# lab07.net
KiCad netlist of a schematic drawn in EAGLE
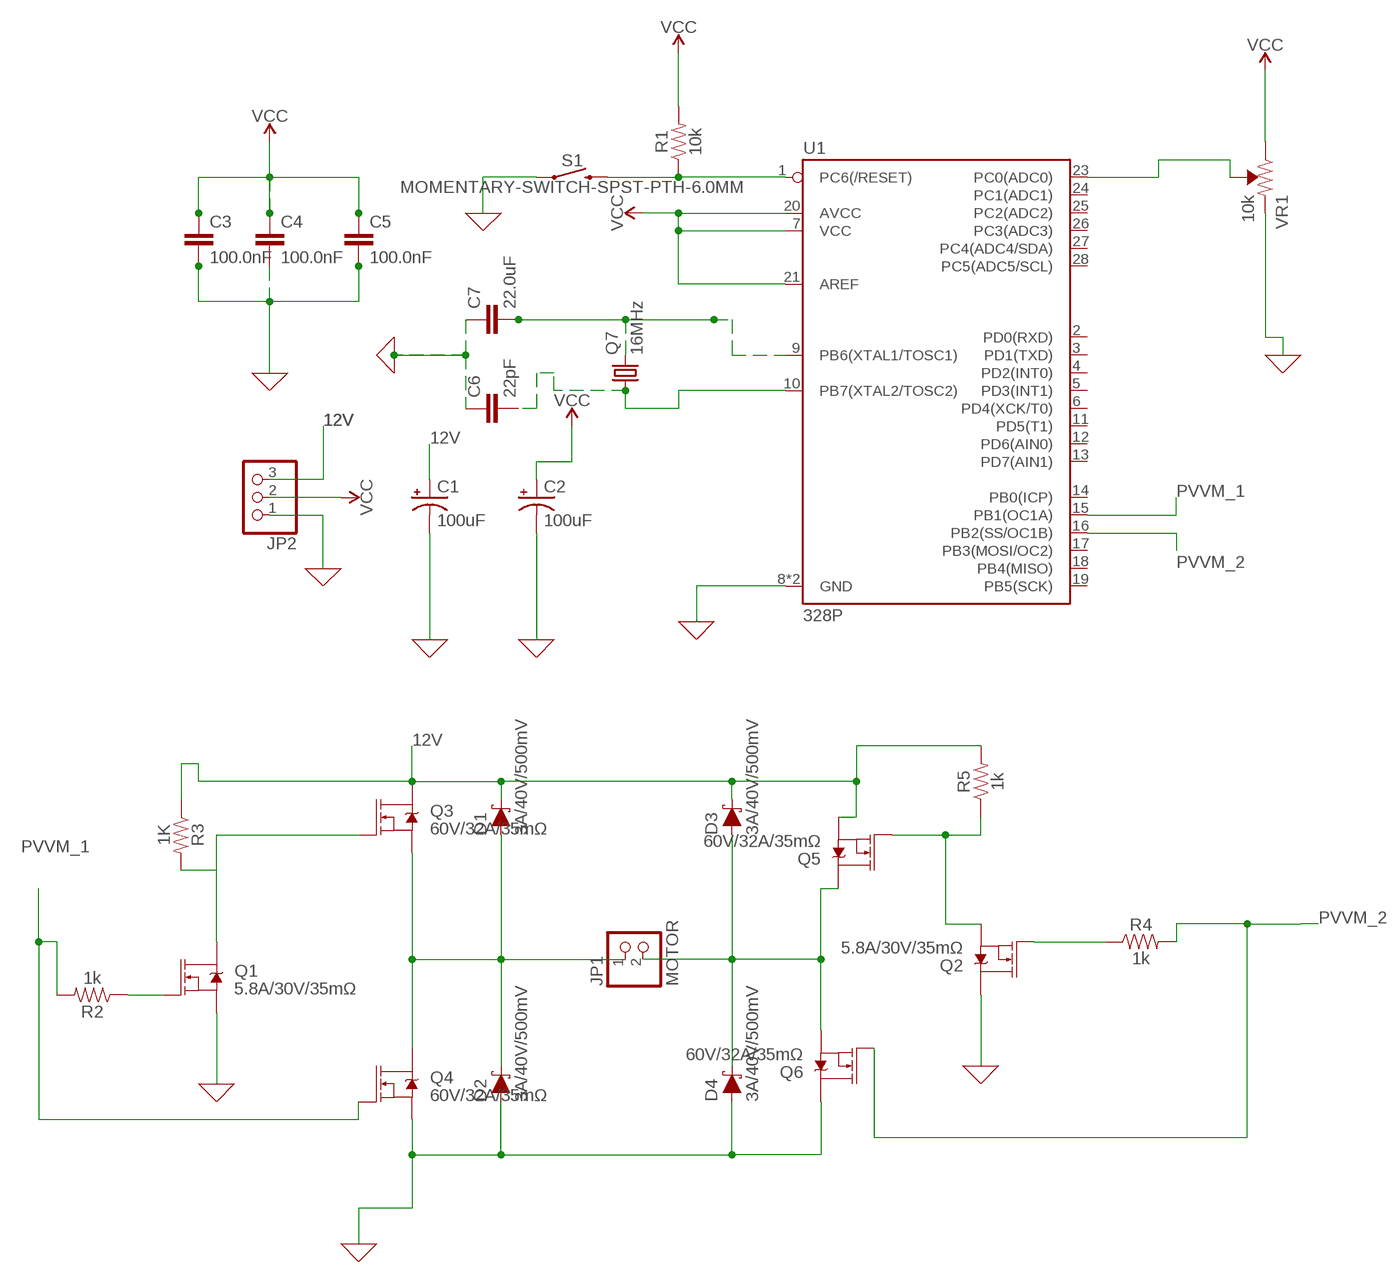
[diagram p0: schematic, sheet 1]

(export (version "E")
  (design (tool "Eeschema 10.0.6"))
  (components
    (comp (ref "C1")
      (value "100uF")
      (footprint "eagle-import:CPOL-RADIAL-2.5MM-5MM")
      (libsource (lib "eagle-import") (part "10UF-POLAR-RADIAL-2.5MM-25V-20%"))
    )
    (comp (ref "C2")
      (value "100uF")
      (footprint "eagle-import:CPOL-RADIAL-2.5MM-5MM")
      (libsource (lib "eagle-import") (part "10UF-POLAR-RADIAL-2.5MM-25V-20%"))
    )
    (comp (ref "C3")
      (value "100.0nF")
      (footprint "eagle-import:0805")
      (libsource (lib "eagle-import") (part "1.0UF-0805-25V-(+80/-20%)"))
    )
    (comp (ref "C4")
      (value "100.0nF")
      (footprint "eagle-import:0805")
      (libsource (lib "eagle-import") (part "1.0UF-0805-25V-(+80/-20%)"))
    )
    (comp (ref "C5")
      (value "100.0nF")
      (footprint "eagle-import:0805")
      (libsource (lib "eagle-import") (part "1.0UF-0805-25V-(+80/-20%)"))
    )
    (comp (ref "C6")
      (value "22pF")
      (footprint "eagle-import:0805")
      (libsource (lib "eagle-import") (part "1.0UF-0805-25V-(+80/-20%)"))
    )
    (comp (ref "C7")
      (value "22.0uF")
      (footprint "eagle-import:0805")
      (libsource (lib "eagle-import") (part "1.0UF-0805-25V-(+80/-20%)"))
    )
    (comp (ref "D1")
      (value "3A/40V/500mV")
      (footprint "eagle-import:SMA-DIODE")
      (libsource (lib "eagle-import") (part "DIODE-SCHOTTKY-B340A"))
    )
    (comp (ref "D2")
      (value "3A/40V/500mV")
      (footprint "eagle-import:SMA-DIODE")
      (libsource (lib "eagle-import") (part "DIODE-SCHOTTKY-B340A"))
    )
    (comp (ref "D3")
      (value "3A/40V/500mV")
      (footprint "eagle-import:SMA-DIODE")
      (libsource (lib "eagle-import") (part "DIODE-SCHOTTKY-B340A"))
    )
    (comp (ref "D4")
      (value "3A/40V/500mV")
      (footprint "eagle-import:SMA-DIODE")
      (libsource (lib "eagle-import") (part "DIODE-SCHOTTKY-B340A"))
    )
    (comp (ref "JP1")
      (value "MOTOR")
      (footprint "eagle-import:1X02")
      (libsource (lib "eagle-import") (part "PINHD-1X2"))
    )
    (comp (ref "JP2")
      (value "PINHD-1X3")
      (footprint "eagle-import:1X03")
      (libsource (lib "eagle-import") (part "PINHD-1X3"))
    )
    (comp (ref "Q1")
      (value "5.8A/30V/35mΩ")
      (footprint "eagle-import:SOT23-3")
      (libsource (lib "eagle-import") (part "MOSFET-NCH-AO3404A"))
    )
    (comp (ref "Q2")
      (value "5.8A/30V/35mΩ")
      (footprint "eagle-import:SOT23-3")
      (libsource (lib "eagle-import") (part "MOSFET-NCH-AO3404A"))
    )
    (comp (ref "Q3")
      (value "60V/32A/35mΩ")
      (footprint "eagle-import:TO220V")
      (libsource (lib "eagle-import") (part "MOSFET-NCH-FQP30N06L"))
    )
    (comp (ref "Q4")
      (value "60V/32A/35mΩ")
      (footprint "eagle-import:TO220V")
      (libsource (lib "eagle-import") (part "MOSFET-NCH-FQP30N06L"))
    )
    (comp (ref "Q5")
      (value "60V/32A/35mΩ")
      (footprint "eagle-import:TO220V")
      (fields (field (name "SPICEPREFIX") "Q"))
      (libsource (lib "eagle-import") (part "MOSFET-NCH-FQP30N06L"))
    )
    (comp (ref "Q6")
      (value "60V/32A/35mΩ")
      (footprint "eagle-import:TO220V")
      (libsource (lib "eagle-import") (part "MOSFET-NCH-FQP30N06L"))
    )
    (comp (ref "Q7")
      (value "16MHz")
      (footprint "eagle-import:HC49_S")
      (libsource (lib "eagle-import") (part "CRYSTALHC49S"))
    )
    (comp (ref "R1")
      (value "10k")
      (footprint "eagle-import:1210")
      (libsource (lib "eagle-import") (part "0.1OHM-1210-1/2W-1%"))
    )
    (comp (ref "R2")
      (value "1k")
      (footprint "eagle-import:1210")
      (libsource (lib "eagle-import") (part "0.1OHM-1210-1/2W-1%"))
    )
    (comp (ref "R3")
      (value "1K")
      (footprint "eagle-import:1210")
      (libsource (lib "eagle-import") (part "0.1OHM-1210-1/2W-1%"))
    )
    (comp (ref "R4")
      (value "1k")
      (footprint "eagle-import:1210")
      (libsource (lib "eagle-import") (part "0.1OHM-1210-1/2W-1%"))
    )
    (comp (ref "R5")
      (value "1k")
      (footprint "eagle-import:1210")
      (libsource (lib "eagle-import") (part "0.1OHM-1210-1/2W-1%"))
    )
    (comp (ref "S1")
      (value "MOMENTARY-SWITCH-SPST-PTH-6.0MM")
      (footprint "eagle-import:TACTILE_SWITCH_PTH_6.0MM")
      (libsource (lib "eagle-import") (part "MOMENTARY-SWITCH-SPST-PTH-6.0MM"))
    )
    (comp (ref "U1")
      (value "328P")
      (footprint "eagle-import:DIP28")
      (libsource (lib "eagle-import") (part "ATMEGA328P_PDIP"))
    )
    (comp (ref "VR1")
      (value "10k")
      (footprint "eagle-import:TRIMPOT-PTH-3386U")
      (libsource (lib "eagle-import") (part "TRIMPOT-PTH-10MM-KNOB-1/2W-10%"))
    )
  )
  (nets
    (net (code "1") (name "/12V") (class "Default")
      (node (ref "C1") (pin "1") (pinfunction "+_1") (pintype "passive"))
      (node (ref "D1") (pin "C") (pinfunction "C_C") (pintype "passive"))
      (node (ref "D3") (pin "C") (pinfunction "C_C") (pintype "passive"))
      (node (ref "JP2") (pin "3") (pinfunction "3_3") (pintype "passive"))
      (node (ref "Q3") (pin "2") (pinfunction "D_2") (pintype "bidirectional"))
      (node (ref "Q5") (pin "3") (pinfunction "S_3") (pintype "bidirectional"))
      (node (ref "R3") (pin "1") (pinfunction "1_1") (pintype "passive"))
      (node (ref "R5") (pin "2") (pinfunction "2_2") (pintype "passive"))
    )
    (net (code "2") (name "/PVVM_1") (class "Default")
      (node (ref "Q4") (pin "1") (pinfunction "G_1") (pintype "bidirectional"))
      (node (ref "R2") (pin "2") (pinfunction "2_2") (pintype "passive"))
      (node (ref "U1") (pin "15") (pinfunction "PB1(OC1A)_15") (pintype "bidirectional"))
    )
    (net (code "3") (name "/PVVM_2") (class "Default")
      (node (ref "Q6") (pin "1") (pinfunction "G_1") (pintype "bidirectional"))
      (node (ref "R4") (pin "2") (pinfunction "2_2") (pintype "passive"))
      (node (ref "U1") (pin "16") (pinfunction "PB2(SS/OC1B)_16") (pintype "bidirectional"))
    )
    (net (code "4") (name "GND") (class "Default")
      (node (ref "C1") (pin "2") (pinfunction "-_2") (pintype "passive"))
      (node (ref "C2") (pin "2") (pinfunction "-_2") (pintype "passive"))
      (node (ref "C3") (pin "2") (pinfunction "2_2") (pintype "passive"))
      (node (ref "C4") (pin "2") (pinfunction "2_2") (pintype "passive"))
      (node (ref "C5") (pin "2") (pinfunction "2_2") (pintype "passive"))
      (node (ref "C6") (pin "1") (pinfunction "1_1") (pintype "passive"))
      (node (ref "C7") (pin "1") (pinfunction "1_1") (pintype "passive"))
      (node (ref "D2") (pin "A") (pinfunction "A_A") (pintype "passive"))
      (node (ref "D4") (pin "A") (pinfunction "A_A") (pintype "passive"))
      (node (ref "JP2") (pin "1") (pinfunction "1_1") (pintype "passive"))
      (node (ref "Q1") (pin "2") (pinfunction "S_2") (pintype "bidirectional"))
      (node (ref "Q2") (pin "3") (pinfunction "D_3") (pintype "bidirectional"))
      (node (ref "Q4") (pin "3") (pinfunction "S_3") (pintype "bidirectional"))
      (node (ref "Q6") (pin "2") (pinfunction "D_2") (pintype "bidirectional"))
      (node (ref "S1") (pin "1") (pinfunction "1_1") (pintype "passive"))
      (node (ref "U1") (pin "22") (pinfunction "GND_22") (pintype "bidirectional"))
      (node (ref "U1") (pin "8") (pinfunction "GND_8") (pintype "bidirectional"))
      (node (ref "VR1") (pin "1") (pinfunction "CCW_1") (pintype "passive"))
    )
    (net (code "5") (name "Net-(Q1-D)") (class "Default")
      (node (ref "Q1") (pin "3") (pinfunction "D_3") (pintype "bidirectional"))
      (node (ref "Q3") (pin "1") (pinfunction "G_1") (pintype "bidirectional"))
      (node (ref "R3") (pin "2") (pinfunction "2_2") (pintype "passive"))
    )
    (net (code "6") (name "Net-(Q1-G)") (class "Default")
      (node (ref "Q1") (pin "1") (pinfunction "G_1") (pintype "bidirectional"))
      (node (ref "R2") (pin "1") (pinfunction "1_1") (pintype "passive"))
    )
    (net (code "7") (name "Net-(Q2-G)") (class "Default")
      (node (ref "Q2") (pin "1") (pinfunction "G_1") (pintype "bidirectional"))
      (node (ref "R4") (pin "1") (pinfunction "1_1") (pintype "passive"))
    )
    (net (code "8") (name "Net-(Q2-S)") (class "Default")
      (node (ref "Q2") (pin "2") (pinfunction "S_2") (pintype "bidirectional"))
      (node (ref "Q5") (pin "1") (pinfunction "G_1") (pintype "bidirectional"))
      (node (ref "R5") (pin "1") (pinfunction "1_1") (pintype "passive"))
    )
    (net (code "9") (name "Net-(Q3-S)") (class "Default")
      (node (ref "D1") (pin "A") (pinfunction "A_A") (pintype "passive"))
      (node (ref "D2") (pin "C") (pinfunction "C_C") (pintype "passive"))
      (node (ref "JP1") (pin "1") (pinfunction "1_1") (pintype "passive"))
      (node (ref "Q3") (pin "3") (pinfunction "S_3") (pintype "bidirectional"))
      (node (ref "Q4") (pin "2") (pinfunction "D_2") (pintype "bidirectional"))
    )
    (net (code "10") (name "Net-(Q5-D)") (class "Default")
      (node (ref "D3") (pin "A") (pinfunction "A_A") (pintype "passive"))
      (node (ref "D4") (pin "C") (pinfunction "C_C") (pintype "passive"))
      (node (ref "JP1") (pin "2") (pinfunction "2_2") (pintype "passive"))
      (node (ref "Q5") (pin "2") (pinfunction "D_2") (pintype "bidirectional"))
      (node (ref "Q6") (pin "3") (pinfunction "S_3") (pintype "bidirectional"))
    )
    (net (code "11") (name "Net-(S1-2)") (class "Default")
      (node (ref "R1") (pin "1") (pinfunction "1_1") (pintype "passive"))
      (node (ref "S1") (pin "3") (pinfunction "2_3") (pintype "passive"))
      (node (ref "U1") (pin "1") (pinfunction "PC6(/RESET)_1") (pintype "bidirectional"))
    )
    (net (code "12") (name "Net-(U1-PB6(XTAL1{slash}TOSC1))") (class "Default")
      (node (ref "C7") (pin "2") (pinfunction "2_2") (pintype "passive"))
      (node (ref "Q7") (pin "2") (pinfunction "2_2") (pintype "passive"))
      (node (ref "U1") (pin "9") (pinfunction "PB6(XTAL1/TOSC1)_9") (pintype "bidirectional"))
    )
    (net (code "13") (name "Net-(U1-PB7(XTAL2{slash}TOSC2))") (class "Default")
      (node (ref "C6") (pin "2") (pinfunction "2_2") (pintype "passive"))
      (node (ref "Q7") (pin "1") (pinfunction "1_1") (pintype "passive"))
      (node (ref "U1") (pin "10") (pinfunction "PB7(XTAL2/TOSC2)_10") (pintype "bidirectional"))
    )
    (net (code "14") (name "Net-(U1-PC0(ADC0))") (class "Default")
      (node (ref "U1") (pin "23") (pinfunction "PC0(ADC0)_23") (pintype "bidirectional"))
      (node (ref "VR1") (pin "2") (pinfunction "WIPER_2") (pintype "passive"))
    )
    (net (code "15") (name "VCC") (class "Default")
      (node (ref "C2") (pin "1") (pinfunction "+_1") (pintype "passive"))
      (node (ref "C3") (pin "1") (pinfunction "1_1") (pintype "passive"))
      (node (ref "C4") (pin "1") (pinfunction "1_1") (pintype "passive"))
      (node (ref "C5") (pin "1") (pinfunction "1_1") (pintype "passive"))
      (node (ref "JP2") (pin "2") (pinfunction "2_2") (pintype "passive"))
      (node (ref "R1") (pin "2") (pinfunction "2_2") (pintype "passive"))
      (node (ref "U1") (pin "20") (pinfunction "AVCC_20") (pintype "bidirectional"))
      (node (ref "U1") (pin "21") (pinfunction "AREF_21") (pintype "bidirectional"))
      (node (ref "U1") (pin "7") (pinfunction "VCC_7") (pintype "bidirectional"))
      (node (ref "VR1") (pin "3") (pinfunction "CW_3") (pintype "passive"))
    )
    (net (code "16") (name "unconnected-(U1-PB0(ICP)-Pad14)") (class "Default")
      (node (ref "U1") (pin "14") (pinfunction "PB0(ICP)_14") (pintype "bidirectional"))
    )
    (net (code "17") (name "unconnected-(U1-PB3(MOSI{slash}OC2)-Pad17)") (class "Default")
      (node (ref "U1") (pin "17") (pinfunction "PB3(MOSI/OC2)_17") (pintype "bidirectional"))
    )
    (net (code "18") (name "unconnected-(U1-PB4(MISO)-Pad18)") (class "Default")
      (node (ref "U1") (pin "18") (pinfunction "PB4(MISO)_18") (pintype "bidirectional"))
    )
    (net (code "19") (name "unconnected-(U1-PB5(SCK)-Pad19)") (class "Default")
      (node (ref "U1") (pin "19") (pinfunction "PB5(SCK)_19") (pintype "bidirectional"))
    )
    (net (code "20") (name "unconnected-(U1-PC1(ADC1)-Pad24)") (class "Default")
      (node (ref "U1") (pin "24") (pinfunction "PC1(ADC1)_24") (pintype "bidirectional"))
    )
    (net (code "21") (name "unconnected-(U1-PC2(ADC2)-Pad25)") (class "Default")
      (node (ref "U1") (pin "25") (pinfunction "PC2(ADC2)_25") (pintype "bidirectional"))
    )
    (net (code "22") (name "unconnected-(U1-PC3(ADC3)-Pad26)") (class "Default")
      (node (ref "U1") (pin "26") (pinfunction "PC3(ADC3)_26") (pintype "bidirectional"))
    )
    (net (code "23") (name "unconnected-(U1-PC4(ADC4{slash}SDA)-Pad27)") (class "Default")
      (node (ref "U1") (pin "27") (pinfunction "PC4(ADC4/SDA)_27") (pintype "bidirectional"))
    )
    (net (code "24") (name "unconnected-(U1-PC5(ADC5{slash}SCL)-Pad28)") (class "Default")
      (node (ref "U1") (pin "28") (pinfunction "PC5(ADC5/SCL)_28") (pintype "bidirectional"))
    )
    (net (code "25") (name "unconnected-(U1-PD0(RXD)-Pad2)") (class "Default")
      (node (ref "U1") (pin "2") (pinfunction "PD0(RXD)_2") (pintype "bidirectional"))
    )
    (net (code "26") (name "unconnected-(U1-PD1(TXD)-Pad3)") (class "Default")
      (node (ref "U1") (pin "3") (pinfunction "PD1(TXD)_3") (pintype "bidirectional"))
    )
    (net (code "27") (name "unconnected-(U1-PD2(INT0)-Pad4)") (class "Default")
      (node (ref "U1") (pin "4") (pinfunction "PD2(INT0)_4") (pintype "bidirectional"))
    )
    (net (code "28") (name "unconnected-(U1-PD3(INT1)-Pad5)") (class "Default")
      (node (ref "U1") (pin "5") (pinfunction "PD3(INT1)_5") (pintype "bidirectional"))
    )
    (net (code "29") (name "unconnected-(U1-PD4(XCK{slash}T0)-Pad6)") (class "Default")
      (node (ref "U1") (pin "6") (pinfunction "PD4(XCK/T0)_6") (pintype "bidirectional"))
    )
    (net (code "30") (name "unconnected-(U1-PD5(T1)-Pad11)") (class "Default")
      (node (ref "U1") (pin "11") (pinfunction "PD5(T1)_11") (pintype "bidirectional"))
    )
    (net (code "31") (name "unconnected-(U1-PD6(AIN0)-Pad12)") (class "Default")
      (node (ref "U1") (pin "12") (pinfunction "PD6(AIN0)_12") (pintype "bidirectional"))
    )
    (net (code "32") (name "unconnected-(U1-PD7(AIN1)-Pad13)") (class "Default")
      (node (ref "U1") (pin "13") (pinfunction "PD7(AIN1)_13") (pintype "bidirectional"))
    )
  )
)
